# FRAM.net
KiCad netlist of a schematic drawn in Altium Designer
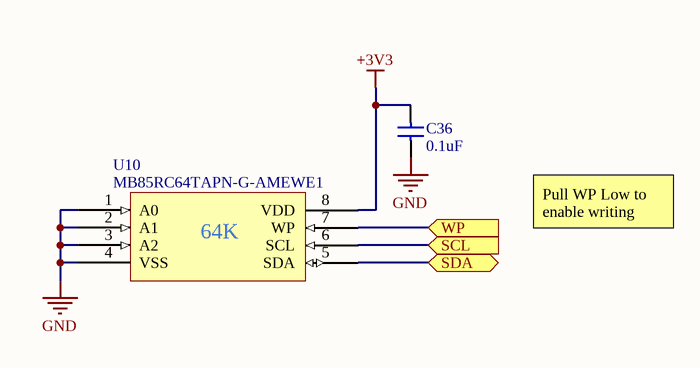
[diagram p0: FRAM.SchDoc]

(export (version "E")
  (design (tool "Eeschema 10.0.6"))
  (components
    (comp (ref "C36")
      (value "0.1uF")
      (footprint "0603_CAPACITOR")
      (description "CAP CERM 0.1uF 10% 50V 0603")
      (fields
        (field (name "VOLTAGE") "50V")
        (field (name "Comment") "CAP 0.1uF 50V X7R")
        (field (name "SVP CREATOR") "Spencer Berglund")
      )
      (libsource (lib "capacitor") (part "C_0603_0.1uF_50V_10%"))
    )
    (comp (ref "U10")
      (value "MB85RC64TAPN-G-AMEWE1")
      (footprint "WFDFN-8-EP-Long")
      (description "FRAM (Ferroelectric RAM) Memory IC 64Kb (8K x 8) I²C 3.4MHz 8-SON")
      (fields (field (name "MANUFACTURER") "Fujitsu"))
      (libsource (lib "ic") (part "U_MB85RC64TA"))
    )
  )
  (nets
    (net (code "1") (name "+3V3") (class "Default")
      (node (ref "C36") (pin "1") (pinfunction "1_1") (pintype "passive"))
      (node (ref "U10") (pin "8") (pinfunction "VDD_8") (pintype "power_in"))
    )
    (net (code "2") (name "/SCL") (class "Default")
      (node (ref "U10") (pin "6") (pinfunction "SCL_6") (pintype "input"))
    )
    (net (code "3") (name "/SDA") (class "Default")
      (node (ref "U10") (pin "5") (pinfunction "SDA_5") (pintype "bidirectional"))
    )
    (net (code "4") (name "/WP") (class "Default")
      (node (ref "U10") (pin "7") (pinfunction "WP_7") (pintype "input"))
    )
    (net (code "5") (name "GND") (class "Default")
      (node (ref "C36") (pin "2") (pinfunction "2_2") (pintype "passive"))
      (node (ref "U10") (pin "1") (pinfunction "A0_1") (pintype "input"))
      (node (ref "U10") (pin "2") (pinfunction "A1_2") (pintype "input"))
      (node (ref "U10") (pin "3") (pinfunction "A2_3") (pintype "input"))
      (node (ref "U10") (pin "4") (pinfunction "VSS_4") (pintype "power_in"))
    )
  )
)
